# YakupTrkn.net
KiCad netlist of a schematic drawn in Altium Designer
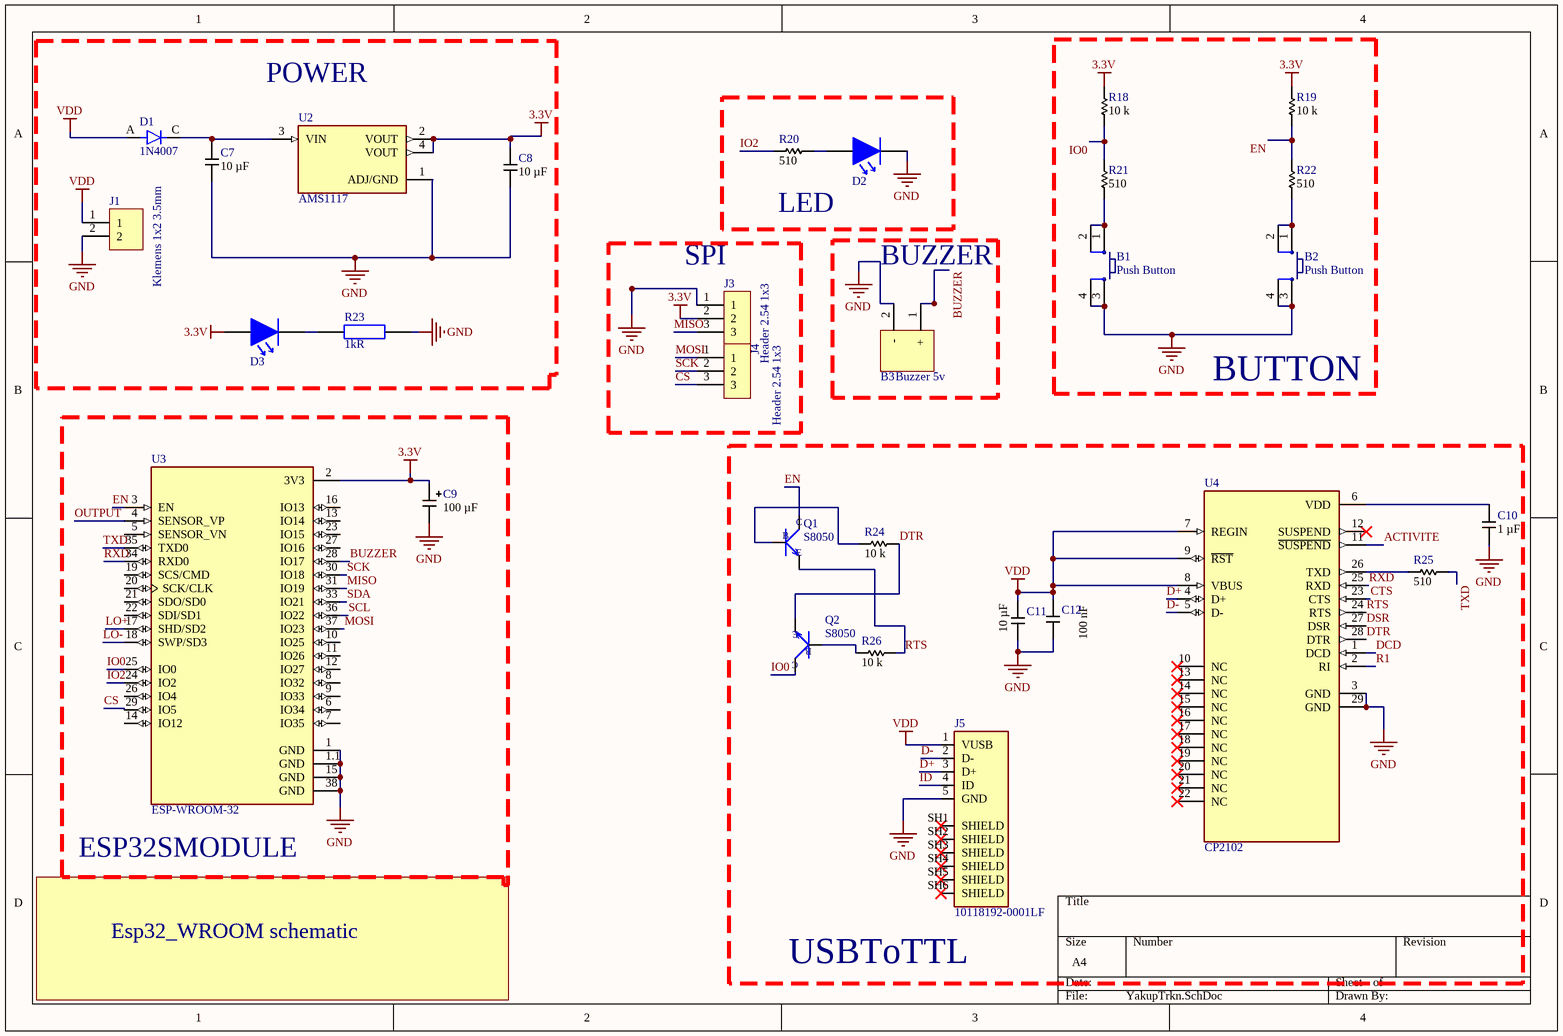
[diagram p0: YakupTrkn.SchDoc]

(export (version "E")
  (design (tool "Eeschema 10.0.6"))
  (components
    (comp (ref "B1")
      (value "Push Button")
      (footprint "PUSB BUTTON-SMD")
      (description "Smd Push Button")
      (libsource (lib "YakupTrkn") (part "Push Button"))
    )
    (comp (ref "B2")
      (value "Push Button")
      (footprint "PUSB BUTTON-SMD")
      (description "Smd Push Button")
      (libsource (lib "YakupTrkn") (part "Push Button"))
    )
    (comp (ref "B3")
      (value "Buzzer 5v")
      (footprint "Buzzer 5v")
      (libsource (lib "YakupTrkn") (part "Buzzer 5v"))
    )
    (comp (ref "C7")
      (value "CL21B106KPQNNNE")
      (footprint "SAMSUNG_CAP_0805_140")
      (description "CAP CER 10UF 10V X7R 0805")
      (fields (field (name "CAPACITANCE") "10 µF"))
      (libsource (lib "YakupTrkn") (part "CL21B106KPQNNNE"))
    )
    (comp (ref "C8")
      (value "CL21B106KPQNNNE")
      (footprint "SAMSUNG_CAP_0805_140")
      (description "CAP CER 10UF 10V X7R 0805")
      (fields (field (name "CAPACITANCE") "10 µF"))
      (libsource (lib "YakupTrkn") (part "CL21B106KPQNNNE"))
    )
    (comp (ref "C9")
      (value "T491B107K006AT")
      (footprint "KEMET_CAP_TAN-B")
      (description "CAP TANT 100UF 10% 6.3V 1411")
      (fields (field (name "CAPACITANCE") "100 µF"))
      (libsource (lib "YakupTrkn") (part "T491B107K006AT"))
    )
    (comp (ref "C10")
      (value "CL21B105KBFNNNE")
      (footprint "SAMSUNG_CAP_0805_135")
      (description "CAP CER 1UF 50V X7R 0805")
      (fields (field (name "CAPACITANCE") "1 µF"))
      (libsource (lib "YakupTrkn") (part "CL21B105KBFNNNE"))
    )
    (comp (ref "C11")
      (value "CL21B106KPQNNNE")
      (footprint "SAMSUNG_CAP_0805_140")
      (description "CAP CER 10UF 10V X7R 0805")
      (fields (field (name "CAPACITANCE") "10 µF"))
      (libsource (lib "YakupTrkn") (part "CL21B106KPQNNNE"))
    )
    (comp (ref "C12")
      (value "CL21B222KBANNNC")
      (footprint "SAMSUNG_CAP_0805_075")
      (description "CAP CER 100NnF 50V X7R 0805")
      (fields (field (name "CAPACITANCE") "100 nF"))
      (libsource (lib "YakupTrkn") (part "CL21B222KBANNNC"))
    )
    (comp (ref "D1")
      (value "1N4007")
      (footprint "1N4007:DIOAD1060W80L520D270")
      (description "Diode Switching 1KV 1A 2-Pin DO-41")
      (fields (field (name "MF") "{'manufacturer': u'ON Semiconductor'}"))
      (libsource (lib "YakupTrkn") (part "1N4007"))
    )
    (comp (ref "D2")
      (value "LTST-C171GKT")
      (footprint "LED_GREEN_0805")
      (description "Green 0805 130 º Min 5 mcd Typical 12 mcd Water Clear Lens SMT LED")
      (fields (field (name "MANUFACTURER") "Vishay Lite-On") (field (name "DESIGNED BY") "BERK"))
      (libsource (lib "YakupTrkn") (part "LED GREEN 0805"))
    )
    (comp (ref "D3")
      (value "LH R974-LP-1")
      (footprint "LED_RED_0805")
      (description "LED Uni-Color Hyper Red 660nm 2-Pin Chip 0805(2012Metric) T/R")
      (fields (field (name "MANUFACTURER") "Osram Opto") (field (name "DESIGNED BY") "BERK"))
      (libsource (lib "YakupTrkn") (part "LED RED 0805"))
    )
    (comp (ref "J1")
      (value "Klemens 1x2 3.5mm")
      (footprint "Klemens 1x2 - 3.5mm")
      (libsource (lib "YakupTrkn") (part "Klemens 1x2 3.5mm"))
    )
    (comp (ref "J3")
      (value "Header 2.54 1x3")
      (footprint "Header 2.54 1x3")
      (libsource (lib "YakupTrkn") (part "Header 2.54 1x3"))
    )
    (comp (ref "J4")
      (value "Header 2.54 1x3")
      (footprint "Header 2.54 1x3")
      (libsource (lib "YakupTrkn") (part "Header 2.54 1x3"))
    )
    (comp (ref "J5")
      (value "10118192-0001LF")
      (footprint "10118192-0001LF:AMPHENOL_10118192-0001LF")
      (description "Single Port 5 Contact Horizontal Right Angle Shielded Micro B USB 2.0 Connector")
      (fields (field (name "MF") "{'manufacturer': u'FCI'}"))
      (libsource (lib "YakupTrkn") (part "10118192-0001LF"))
    )
    (comp (ref "Q1")
      (value "S8050")
      (footprint "S8050:SOT-23")
      (description "305010017")
      (fields (field (name "MF") "{'manufacturer': u'UMW'}"))
      (libsource (lib "YakupTrkn") (part "SMD-TRANSISTORS-NPN-25V-500MW(SOT-23)"))
    )
    (comp (ref "Q2")
      (value "S8050")
      (footprint "S8050:SOT-23")
      (description "305010017")
      (fields (field (name "MF") "{'manufacturer': u'UMW'}"))
      (libsource (lib "YakupTrkn") (part "SMD-TRANSISTORS-NPN-25V-500MW(SOT-23)"))
    )
    (comp (ref "R18")
      (value "0805S8J0103T5E")
      (footprint "ROYALOHM_RES_0805")
      (description "RES SMD 10K OHM 5% 1/8W 0805")
      (fields (field (name "RESISTANCE") "10 k"))
      (libsource (lib "YakupTrkn") (part "0805S8J0103T5E"))
    )
    (comp (ref "R19")
      (value "0805S8J0103T5E")
      (footprint "ROYALOHM_RES_0805")
      (description "RES SMD 10K OHM 5% 1/8W 0805")
      (fields (field (name "RESISTANCE") "10 k"))
      (libsource (lib "YakupTrkn") (part "0805S8J0103T5E"))
    )
    (comp (ref "R20")
      (value "1206S4F5100T5E")
      (footprint "ROYALOHM_RES_1206")
      (description "RES SMD 510 OHM 1% 1/4W 1206")
      (fields (field (name "RESISTANCE") "510"))
      (libsource (lib "YakupTrkn") (part "1206S4F5100T5E"))
    )
    (comp (ref "R21")
      (value "1206S4F5100T5E")
      (footprint "ROYALOHM_RES_1206")
      (description "RES SMD 510 OHM 1% 1/4W 1206")
      (fields (field (name "RESISTANCE") "510"))
      (libsource (lib "YakupTrkn") (part "1206S4F5100T5E"))
    )
    (comp (ref "R22")
      (value "1206S4F5100T5E")
      (footprint "ROYALOHM_RES_1206")
      (description "RES SMD 510 OHM 1% 1/4W 1206")
      (fields (field (name "RESISTANCE") "510"))
      (libsource (lib "YakupTrkn") (part "1206S4F5100T5E"))
    )
    (comp (ref "R23")
      (value "RC0603FR-0710KL")
      (footprint "RES_0603")
      (description "RES 1K %1 OHM 0603 SMD")
      (fields
        (field (name "MANUFACTURER") "Yageo")
        (field (name "MANUFACTURER PART NUMBER") "RC0603JR-071KL")
        (field (name "RESISTANCE") "1kR")
        (field (name "DESIGNED BY") "BERK")
      )
      (libsource (lib "YakupTrkn") (part "RES 1K OHM 0603"))
    )
    (comp (ref "R24")
      (value "0805S8J0103T5E")
      (footprint "ROYALOHM_RES_0805")
      (description "RES SMD 10K OHM 5% 1/8W 0805")
      (fields (field (name "RESISTANCE") "10 k"))
      (libsource (lib "YakupTrkn") (part "0805S8J0103T5E"))
    )
    (comp (ref "R25")
      (value "1206S4F5100T5E")
      (footprint "ROYALOHM_RES_1206")
      (description "RES SMD 510 OHM 1% 1/4W 1206")
      (fields (field (name "RESISTANCE") "510"))
      (libsource (lib "YakupTrkn") (part "1206S4F5100T5E"))
    )
    (comp (ref "R26")
      (value "0805S8J0103T5E")
      (footprint "ROYALOHM_RES_0805")
      (description "RES SMD 10K OHM 5% 1/8W 0805")
      (fields (field (name "RESISTANCE") "10 k"))
      (libsource (lib "YakupTrkn") (part "0805S8J0103T5E"))
    )
    (comp (ref "U2")
      (value "AMS1117")
      (footprint "AMS1117:SOT229P700X180-4N")
      (description "Sot223/Pkg 1-Amp 5-Volt Low Drop Out Voltage Regulatator")
      (fields (field (name "MF") "{'manufacturer': u'Advanced Monolithic Systems'}"))
      (libsource (lib "YakupTrkn") (part "AMS1117"))
    )
    (comp (ref "U3")
      (value "ESP-WROOM-32")
      (footprint "ESP-WROOM-32:MODULE_ESP-WROOM-32")
      (description "Module: combo; GPIO, I2C x2, I2S x2, SDIO, SPI x3, UART x3; 19.5dBm")
      (fields (field (name "MF") "{'manufacturer': u'Olimex LTD'}"))
      (libsource (lib "YakupTrkn") (part "ESP-WROOM-32"))
    )
    (comp (ref "U4")
      (value "CP2102")
      (footprint "CP2102:QFN50P500X500X100-29N")
      (description "USB to UART Bridge")
      (fields (field (name "MF") "{'manufacturer': u'Silicon Labs'}"))
      (libsource (lib "YakupTrkn") (part "CP2102"))
    )
  )
  (nets
    (net (code "1") (name "/ACTIVITE") (class "Default")
      (node (ref "U4") (pin "11") (pinfunction "~{SUSPEND}_11") (pintype "output"))
    )
    (net (code "2") (name "/BUZZER") (class "Default")
      (node (ref "B3") (pin "1") (pinfunction "+_1") (pintype "passive"))
      (node (ref "U3") (pin "28") (pinfunction "IO17_28") (pintype "bidirectional"))
    )
    (net (code "3") (name "/CS") (class "Default")
      (node (ref "J4") (pin "3") (pinfunction "3_3") (pintype "passive"))
      (node (ref "U3") (pin "29") (pinfunction "IO5_29") (pintype "bidirectional"))
    )
    (net (code "4") (name "/CTS") (class "Default")
      (node (ref "U4") (pin "23") (pinfunction "CTS_23") (pintype "input"))
    )
    (net (code "5") (name "/D+") (class "Default")
      (node (ref "J5") (pin "3") (pinfunction "D+_3") (pintype "passive"))
      (node (ref "U4") (pin "4") (pinfunction "D+_4") (pintype "bidirectional"))
    )
    (net (code "6") (name "/D-") (class "Default")
      (node (ref "J5") (pin "2") (pinfunction "D-_2") (pintype "passive"))
      (node (ref "U4") (pin "5") (pinfunction "D-_5") (pintype "bidirectional"))
    )
    (net (code "7") (name "/DCD") (class "Default")
      (node (ref "U4") (pin "1") (pinfunction "DCD_1") (pintype "input"))
    )
    (net (code "8") (name "/DSR") (class "Default")
      (node (ref "U4") (pin "27") (pinfunction "DSR_27") (pintype "input"))
    )
    (net (code "9") (name "/DTR") (class "Default")
      (node (ref "Q2") (pin "2") (pinfunction "E_2") (pintype "passive"))
      (node (ref "R24") (pin "1") (pinfunction "1_1") (pintype "passive"))
      (node (ref "U4") (pin "28") (pinfunction "DTR_28") (pintype "output"))
    )
    (net (code "10") (name "/EN") (class "Default")
      (node (ref "Q1") (pin "3") (pinfunction "C_3") (pintype "passive"))
      (node (ref "R19") (pin "1") (pinfunction "1_1") (pintype "passive"))
      (node (ref "R22") (pin "1") (pinfunction "1_1") (pintype "passive"))
      (node (ref "U3") (pin "3") (pinfunction "EN_3") (pintype "input"))
    )
    (net (code "11") (name "/ID") (class "Default")
      (node (ref "J5") (pin "4") (pinfunction "ID_4") (pintype "passive"))
    )
    (net (code "12") (name "/IO0") (class "Default")
      (node (ref "Q2") (pin "3") (pinfunction "C_3") (pintype "passive"))
      (node (ref "R18") (pin "1") (pinfunction "1_1") (pintype "passive"))
      (node (ref "R21") (pin "1") (pinfunction "1_1") (pintype "passive"))
      (node (ref "U3") (pin "25") (pinfunction "IO0_25") (pintype "bidirectional"))
    )
    (net (code "13") (name "/IO2") (class "Default")
      (node (ref "R20") (pin "1") (pinfunction "1_1") (pintype "passive"))
      (node (ref "U3") (pin "24") (pinfunction "IO2_24") (pintype "bidirectional"))
    )
    (net (code "14") (name "/LO+") (class "Default")
      (node (ref "U3") (pin "17") (pinfunction "SHD/SD2_17") (pintype "bidirectional"))
    )
    (net (code "15") (name "/LO-") (class "Default")
      (node (ref "U3") (pin "18") (pinfunction "SWP/SD3_18") (pintype "bidirectional"))
    )
    (net (code "16") (name "/MISO") (class "Default")
      (node (ref "J3") (pin "3") (pinfunction "3_3") (pintype "passive"))
      (node (ref "U3") (pin "31") (pinfunction "IO19_31") (pintype "bidirectional"))
    )
    (net (code "17") (name "/MOSI") (class "Default")
      (node (ref "J4") (pin "1") (pinfunction "1_1") (pintype "passive"))
      (node (ref "U3") (pin "37") (pinfunction "IO23_37") (pintype "bidirectional"))
    )
    (net (code "18") (name "/OUTPUT") (class "Default")
      (node (ref "U3") (pin "4") (pinfunction "SENSOR_VP_4") (pintype "input"))
    )
    (net (code "19") (name "/R1") (class "Default")
      (node (ref "U4") (pin "2") (pinfunction "RI_2") (pintype "input"))
    )
    (net (code "20") (name "/RTS") (class "Default")
      (node (ref "Q1") (pin "2") (pinfunction "E_2") (pintype "passive"))
      (node (ref "R26") (pin "2") (pinfunction "2_2") (pintype "passive"))
      (node (ref "U4") (pin "24") (pinfunction "RTS_24") (pintype "output"))
    )
    (net (code "21") (name "/RXD") (class "Default")
      (node (ref "U3") (pin "34") (pinfunction "RXD0_34") (pintype "bidirectional"))
      (node (ref "U4") (pin "25") (pinfunction "RXD_25") (pintype "input"))
    )
    (net (code "22") (name "/SCK") (class "Default")
      (node (ref "J4") (pin "2") (pinfunction "2_2") (pintype "passive"))
      (node (ref "U3") (pin "30") (pinfunction "IO18_30") (pintype "bidirectional"))
    )
    (net (code "23") (name "/SCL") (class "Default")
      (node (ref "U3") (pin "36") (pinfunction "IO22_36") (pintype "bidirectional"))
    )
    (net (code "24") (name "/SDA") (class "Default")
      (node (ref "U3") (pin "33") (pinfunction "IO21_33") (pintype "bidirectional"))
    )
    (net (code "25") (name "/TXD") (class "Default")
      (node (ref "R25") (pin "2") (pinfunction "2_2") (pintype "passive"))
      (node (ref "U3") (pin "35") (pinfunction "TXD0_35") (pintype "bidirectional"))
    )
    (net (code "26") (name "3.3V") (class "Default")
      (node (ref "C8") (pin "2") (pinfunction "2_2") (pintype "passive"))
      (node (ref "C9") (pin "1") (pinfunction "1_1") (pintype "passive"))
      (node (ref "D3") (pin "2") (pinfunction "2_2") (pintype "power_in"))
      (node (ref "J3") (pin "2") (pinfunction "2_2") (pintype "passive"))
      (node (ref "R18") (pin "2") (pinfunction "2_2") (pintype "passive"))
      (node (ref "R19") (pin "2") (pinfunction "2_2") (pintype "passive"))
      (node (ref "U2") (pin "2") (pinfunction "VOUT_2") (pintype "output"))
      (node (ref "U2") (pin "4") (pinfunction "VOUT_4") (pintype "output"))
      (node (ref "U3") (pin "2") (pinfunction "3V3_2") (pintype "power_in"))
    )
    (net (code "27") (name "GND") (class "Default")
      (node (ref "B1") (pin "3") (pinfunction "3_3") (pintype "passive"))
      (node (ref "B1") (pin "4") (pinfunction "4_4") (pintype "passive"))
      (node (ref "B2") (pin "3") (pinfunction "3_3") (pintype "passive"))
      (node (ref "B2") (pin "4") (pinfunction "4_4") (pintype "passive"))
      (node (ref "B3") (pin "2") (pinfunction "-_2") (pintype "passive"))
      (node (ref "C10") (pin "2") (pinfunction "2_2") (pintype "passive"))
      (node (ref "C11") (pin "2") (pinfunction "2_2") (pintype "passive"))
      (node (ref "C12") (pin "1") (pinfunction "1_1") (pintype "passive"))
      (node (ref "C7") (pin "1") (pinfunction "1_1") (pintype "passive"))
      (node (ref "C8") (pin "1") (pinfunction "1_1") (pintype "passive"))
      (node (ref "C9") (pin "2") (pinfunction "2_2") (pintype "passive"))
      (node (ref "D2") (pin "1") (pinfunction "1_1") (pintype "power_in"))
      (node (ref "J1") (pin "2") (pinfunction "2_2") (pintype "passive"))
      (node (ref "J3") (pin "1") (pinfunction "1_1") (pintype "passive"))
      (node (ref "J5") (pin "5") (pinfunction "GND_5") (pintype "passive"))
      (node (ref "R23") (pin "1") (pinfunction "1_1") (pintype "passive"))
      (node (ref "U2") (pin "1") (pinfunction "ADJ/GND_1") (pintype "power_in"))
      (node (ref "U3") (pin "1") (pinfunction "GND_1") (pintype "power_in"))
      (node (ref "U3") (pin "1.1") (pinfunction "GND_1.1") (pintype "power_in"))
      (node (ref "U3") (pin "15") (pinfunction "GND_15") (pintype "power_in"))
      (node (ref "U3") (pin "38") (pinfunction "GND_38") (pintype "power_in"))
      (node (ref "U4") (pin "29") (pinfunction "GND_29") (pintype "power_in"))
      (node (ref "U4") (pin "3") (pinfunction "GND_3") (pintype "power_in"))
    )
    (net (code "28") (name "Net-(B1-Pad1)") (class "Default")
      (node (ref "B1") (pin "1") (pinfunction "1_1") (pintype "passive"))
      (node (ref "B1") (pin "2") (pinfunction "2_2") (pintype "passive"))
      (node (ref "R21") (pin "2") (pinfunction "2_2") (pintype "passive"))
    )
    (net (code "29") (name "Net-(B2-Pad1)") (class "Default")
      (node (ref "B2") (pin "1") (pinfunction "1_1") (pintype "passive"))
      (node (ref "B2") (pin "2") (pinfunction "2_2") (pintype "passive"))
      (node (ref "R22") (pin "2") (pinfunction "2_2") (pintype "passive"))
    )
    (net (code "30") (name "Net-(D2-Pad2)") (class "Default")
      (node (ref "D2") (pin "2") (pinfunction "2_2") (pintype "power_in"))
      (node (ref "R20") (pin "2") (pinfunction "2_2") (pintype "passive"))
    )
    (net (code "31") (name "Net-(D3-Pad1)") (class "Default")
      (node (ref "D3") (pin "1") (pinfunction "1_1") (pintype "power_in"))
      (node (ref "R23") (pin "2") (pinfunction "2_2") (pintype "passive"))
    )
    (net (code "32") (name "Net-(Q1-B)") (class "Default")
      (node (ref "Q1") (pin "1") (pinfunction "B_1") (pintype "passive"))
      (node (ref "R24") (pin "2") (pinfunction "2_2") (pintype "passive"))
    )
    (net (code "33") (name "Net-(Q2-B)") (class "Default")
      (node (ref "Q2") (pin "1") (pinfunction "B_1") (pintype "passive"))
      (node (ref "R26") (pin "1") (pinfunction "1_1") (pintype "passive"))
    )
    (net (code "34") (name "Net-(U2-VIN)") (class "Default")
      (node (ref "C7") (pin "2") (pinfunction "2_2") (pintype "passive"))
      (node (ref "D1") (pin "C") (pinfunction "C_C") (pintype "passive"))
      (node (ref "U2") (pin "3") (pinfunction "VIN_3") (pintype "input"))
    )
    (net (code "35") (name "Net-(U4-TXD)") (class "Default")
      (node (ref "R25") (pin "1") (pinfunction "1_1") (pintype "passive"))
      (node (ref "U4") (pin "26") (pinfunction "TXD_26") (pintype "output"))
    )
    (net (code "36") (name "Net-(U4-VDD)") (class "Default")
      (node (ref "C10") (pin "1") (pinfunction "1_1") (pintype "passive"))
      (node (ref "U4") (pin "6") (pinfunction "VDD_6") (pintype "power_in"))
    )
    (net (code "37") (name "VDD") (class "Default")
      (node (ref "C11") (pin "1") (pinfunction "1_1") (pintype "passive"))
      (node (ref "C12") (pin "2") (pinfunction "2_2") (pintype "passive"))
      (node (ref "D1") (pin "A") (pinfunction "A_A") (pintype "passive"))
      (node (ref "J1") (pin "1") (pinfunction "1_1") (pintype "passive"))
      (node (ref "J5") (pin "1") (pinfunction "VUSB_1") (pintype "passive"))
      (node (ref "U4") (pin "7") (pinfunction "REGIN_7") (pintype "input"))
      (node (ref "U4") (pin "8") (pinfunction "VBUS_8") (pintype "input"))
      (node (ref "U4") (pin "9") (pinfunction "~{RST}_9") (pintype "bidirectional"))
    )
    (net (code "38") (name "unconnected-(J5-SHIELD-PadSH1)") (class "Default")
      (node (ref "J5") (pin "SH1") (pinfunction "SHIELD_SH1") (pintype "passive+no_connect"))
    )
    (net (code "39") (name "unconnected-(J5-SHIELD-PadSH2)") (class "Default")
      (node (ref "J5") (pin "SH2") (pinfunction "SHIELD_SH2") (pintype "passive+no_connect"))
    )
    (net (code "40") (name "unconnected-(J5-SHIELD-PadSH3)") (class "Default")
      (node (ref "J5") (pin "SH3") (pinfunction "SHIELD_SH3") (pintype "passive+no_connect"))
    )
    (net (code "41") (name "unconnected-(J5-SHIELD-PadSH4)") (class "Default")
      (node (ref "J5") (pin "SH4") (pinfunction "SHIELD_SH4") (pintype "passive+no_connect"))
    )
    (net (code "42") (name "unconnected-(J5-SHIELD-PadSH5)") (class "Default")
      (node (ref "J5") (pin "SH5") (pinfunction "SHIELD_SH5") (pintype "passive+no_connect"))
    )
    (net (code "43") (name "unconnected-(J5-SHIELD-PadSH6)") (class "Default")
      (node (ref "J5") (pin "SH6") (pinfunction "SHIELD_SH6") (pintype "passive+no_connect"))
    )
    (net (code "44") (name "unconnected-(U3-IO4-Pad26)") (class "Default")
      (node (ref "U3") (pin "26") (pinfunction "IO4_26") (pintype "bidirectional"))
    )
    (net (code "45") (name "unconnected-(U3-IO12-Pad14)") (class "Default")
      (node (ref "U3") (pin "14") (pinfunction "IO12_14") (pintype "bidirectional"))
    )
    (net (code "46") (name "unconnected-(U3-IO13-Pad16)") (class "Default")
      (node (ref "U3") (pin "16") (pinfunction "IO13_16") (pintype "bidirectional"))
    )
    (net (code "47") (name "unconnected-(U3-IO14-Pad13)") (class "Default")
      (node (ref "U3") (pin "13") (pinfunction "IO14_13") (pintype "bidirectional"))
    )
    (net (code "48") (name "unconnected-(U3-IO15-Pad23)") (class "Default")
      (node (ref "U3") (pin "23") (pinfunction "IO15_23") (pintype "bidirectional"))
    )
    (net (code "49") (name "unconnected-(U3-IO16-Pad27)") (class "Default")
      (node (ref "U3") (pin "27") (pinfunction "IO16_27") (pintype "bidirectional"))
    )
    (net (code "50") (name "unconnected-(U3-IO25-Pad10)") (class "Default")
      (node (ref "U3") (pin "10") (pinfunction "IO25_10") (pintype "bidirectional"))
    )
    (net (code "51") (name "unconnected-(U3-IO26-Pad11)") (class "Default")
      (node (ref "U3") (pin "11") (pinfunction "IO26_11") (pintype "bidirectional"))
    )
    (net (code "52") (name "unconnected-(U3-IO27-Pad12)") (class "Default")
      (node (ref "U3") (pin "12") (pinfunction "IO27_12") (pintype "bidirectional"))
    )
    (net (code "53") (name "unconnected-(U3-IO32-Pad8)") (class "Default")
      (node (ref "U3") (pin "8") (pinfunction "IO32_8") (pintype "bidirectional"))
    )
    (net (code "54") (name "unconnected-(U3-IO33-Pad9)") (class "Default")
      (node (ref "U3") (pin "9") (pinfunction "IO33_9") (pintype "bidirectional"))
    )
    (net (code "55") (name "unconnected-(U3-IO34-Pad6)") (class "Default")
      (node (ref "U3") (pin "6") (pinfunction "IO34_6") (pintype "bidirectional"))
    )
    (net (code "56") (name "unconnected-(U3-IO35-Pad7)") (class "Default")
      (node (ref "U3") (pin "7") (pinfunction "IO35_7") (pintype "bidirectional"))
    )
    (net (code "57") (name "unconnected-(U3-SCK{slash}CLK-Pad20)") (class "Default")
      (node (ref "U3") (pin "20") (pinfunction "SCK/CLK_20") (pintype "bidirectional"))
    )
    (net (code "58") (name "unconnected-(U3-SCS{slash}CMD-Pad19)") (class "Default")
      (node (ref "U3") (pin "19") (pinfunction "SCS/CMD_19") (pintype "bidirectional"))
    )
    (net (code "59") (name "unconnected-(U3-SDI{slash}SD1-Pad22)") (class "Default")
      (node (ref "U3") (pin "22") (pinfunction "SDI/SD1_22") (pintype "bidirectional"))
    )
    (net (code "60") (name "unconnected-(U3-SDO{slash}SD0-Pad21)") (class "Default")
      (node (ref "U3") (pin "21") (pinfunction "SDO/SD0_21") (pintype "bidirectional"))
    )
    (net (code "61") (name "unconnected-(U3-SENSOR_VN-Pad5)") (class "Default")
      (node (ref "U3") (pin "5") (pinfunction "SENSOR_VN_5") (pintype "input"))
    )
    (net (code "62") (name "unconnected-(U4-NC-Pad10)") (class "Default")
      (node (ref "U4") (pin "10") (pinfunction "NC_10") (pintype "passive+no_connect"))
    )
    (net (code "63") (name "unconnected-(U4-NC-Pad13)") (class "Default")
      (node (ref "U4") (pin "13") (pinfunction "NC_13") (pintype "passive+no_connect"))
    )
    (net (code "64") (name "unconnected-(U4-NC-Pad14)") (class "Default")
      (node (ref "U4") (pin "14") (pinfunction "NC_14") (pintype "passive+no_connect"))
    )
    (net (code "65") (name "unconnected-(U4-NC-Pad15)") (class "Default")
      (node (ref "U4") (pin "15") (pinfunction "NC_15") (pintype "passive+no_connect"))
    )
    (net (code "66") (name "unconnected-(U4-NC-Pad16)") (class "Default")
      (node (ref "U4") (pin "16") (pinfunction "NC_16") (pintype "passive+no_connect"))
    )
    (net (code "67") (name "unconnected-(U4-NC-Pad17)") (class "Default")
      (node (ref "U4") (pin "17") (pinfunction "NC_17") (pintype "passive+no_connect"))
    )
    (net (code "68") (name "unconnected-(U4-NC-Pad18)") (class "Default")
      (node (ref "U4") (pin "18") (pinfunction "NC_18") (pintype "passive+no_connect"))
    )
    (net (code "69") (name "unconnected-(U4-NC-Pad19)") (class "Default")
      (node (ref "U4") (pin "19") (pinfunction "NC_19") (pintype "passive+no_connect"))
    )
    (net (code "70") (name "unconnected-(U4-NC-Pad20)") (class "Default")
      (node (ref "U4") (pin "20") (pinfunction "NC_20") (pintype "passive+no_connect"))
    )
    (net (code "71") (name "unconnected-(U4-NC-Pad21)") (class "Default")
      (node (ref "U4") (pin "21") (pinfunction "NC_21") (pintype "passive+no_connect"))
    )
    (net (code "72") (name "unconnected-(U4-NC-Pad22)") (class "Default")
      (node (ref "U4") (pin "22") (pinfunction "NC_22") (pintype "passive+no_connect"))
    )
    (net (code "73") (name "unconnected-(U4-SUSPEND-Pad12)") (class "Default")
      (node (ref "U4") (pin "12") (pinfunction "SUSPEND_12") (pintype "output+no_connect"))
    )
  )
)
